# M121.net
KiCad netlist of a schematic drawn in EAGLE
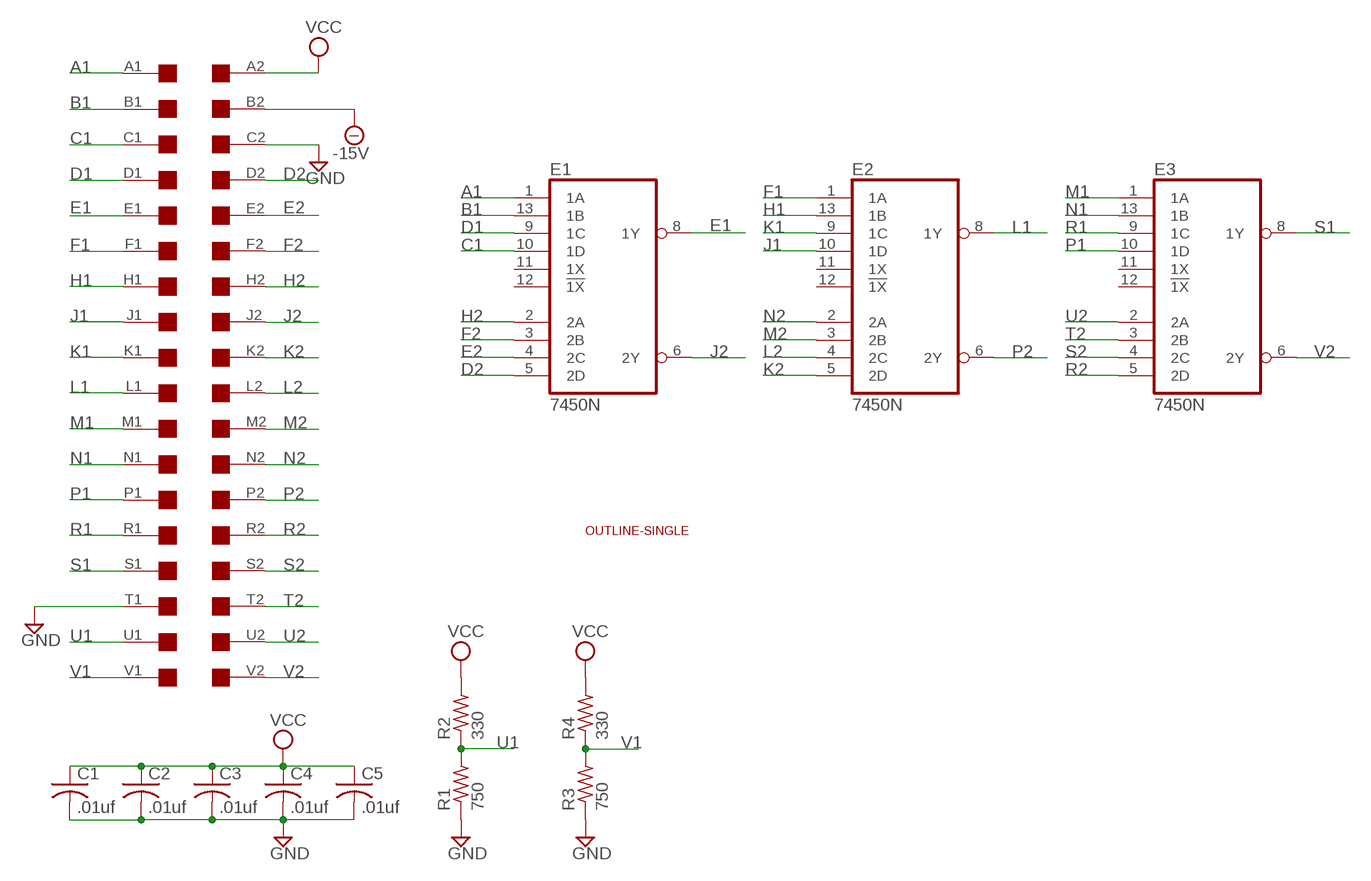
[diagram p0: schematic, sheet 1]

(export (version "E")
  (design (tool "Eeschema 10.0.6"))
  (components
    (comp (ref "C1")
      (value ".01uf")
      (footprint "eagle-import:C050-025X075")
      (libsource (lib "eagle-import") (part "C-US050-025X075"))
    )
    (comp (ref "C2")
      (value ".01uf")
      (footprint "eagle-import:C050-025X075")
      (libsource (lib "eagle-import") (part "C-US050-025X075"))
    )
    (comp (ref "C3")
      (value ".01uf")
      (footprint "eagle-import:C050-025X075")
      (libsource (lib "eagle-import") (part "C-US050-025X075"))
    )
    (comp (ref "C4")
      (value ".01uf")
      (footprint "eagle-import:C050-025X075")
      (libsource (lib "eagle-import") (part "C-US050-025X075"))
    )
    (comp (ref "C5")
      (value ".01uf")
      (footprint "eagle-import:C050-025X075")
      (libsource (lib "eagle-import") (part "C-US050-025X075"))
    )
    (comp (ref "E1")
      (value "7450N")
      (footprint "eagle-import:DIL14")
      (libsource (lib "eagle-import") (part "7450N"))
    )
    (comp (ref "E2")
      (value "7450N")
      (footprint "eagle-import:DIL14")
      (libsource (lib "eagle-import") (part "7450N"))
    )
    (comp (ref "E3")
      (value "7450N")
      (footprint "eagle-import:DIL14")
      (libsource (lib "eagle-import") (part "7450N"))
    )
    (comp (ref "R1")
      (value "750")
      (footprint "eagle-import:0207_10")
      (libsource (lib "eagle-import") (part "R-US_0207/10"))
    )
    (comp (ref "R2")
      (value "330")
      (footprint "eagle-import:0207_10")
      (libsource (lib "eagle-import") (part "R-US_0207/10"))
    )
    (comp (ref "R3")
      (value "750")
      (footprint "eagle-import:0207_10")
      (libsource (lib "eagle-import") (part "R-US_0207/10"))
    )
    (comp (ref "R4")
      (value "330")
      (footprint "eagle-import:0207_10")
      (libsource (lib "eagle-import") (part "R-US_0207/10"))
    )
    (comp (ref "U$1")
      (value "OUTLINE-SINGLE")
      (footprint "eagle-import:SINGLE")
      (libsource (lib "eagle-import") (part "OUTLINE-SINGLE"))
    )
    (comp (ref "U$4")
      (value "SINGLE")
      (footprint "eagle-import:EDGE-CON2")
      (libsource (lib "eagle-import") (part "SINGLE"))
    )
  )
  (nets
    (net (code "1") (name "-15V") (class "Default")
      (node (ref "U$4") (pin "B2") (pinfunction "1_B2") (pintype "bidirectional"))
    )
    (net (code "2") (name "/A1") (class "Default")
      (node (ref "E1") (pin "1") (pinfunction "1A_1") (pintype "input"))
      (node (ref "U$4") (pin "A1") (pinfunction "1_A1") (pintype "bidirectional"))
    )
    (net (code "3") (name "/B1") (class "Default")
      (node (ref "E1") (pin "13") (pinfunction "1B_13") (pintype "input"))
      (node (ref "U$4") (pin "B1") (pinfunction "1_B1") (pintype "bidirectional"))
    )
    (net (code "4") (name "/C1") (class "Default")
      (node (ref "E1") (pin "10") (pinfunction "1D_10") (pintype "input"))
      (node (ref "U$4") (pin "C1") (pinfunction "1_C1") (pintype "bidirectional"))
    )
    (net (code "5") (name "/D1") (class "Default")
      (node (ref "E1") (pin "9") (pinfunction "1C_9") (pintype "input"))
      (node (ref "U$4") (pin "D1") (pinfunction "1_D1") (pintype "bidirectional"))
    )
    (net (code "6") (name "/D2") (class "Default")
      (node (ref "E1") (pin "5") (pinfunction "2D_5") (pintype "input"))
      (node (ref "U$4") (pin "D2") (pinfunction "1_D2") (pintype "bidirectional"))
    )
    (net (code "7") (name "/E1") (class "Default")
      (node (ref "E1") (pin "8") (pinfunction "1Y_8") (pintype "output"))
      (node (ref "U$4") (pin "E1") (pinfunction "1_E1") (pintype "bidirectional"))
    )
    (net (code "8") (name "/E2") (class "Default")
      (node (ref "E1") (pin "4") (pinfunction "2C_4") (pintype "input"))
      (node (ref "U$4") (pin "E2") (pinfunction "1_E2") (pintype "bidirectional"))
    )
    (net (code "9") (name "/F1") (class "Default")
      (node (ref "E2") (pin "1") (pinfunction "1A_1") (pintype "input"))
      (node (ref "U$4") (pin "F1") (pinfunction "1_F1") (pintype "bidirectional"))
    )
    (net (code "10") (name "/F2") (class "Default")
      (node (ref "E1") (pin "3") (pinfunction "2B_3") (pintype "input"))
      (node (ref "U$4") (pin "F2") (pinfunction "1_F2") (pintype "bidirectional"))
    )
    (net (code "11") (name "/H1") (class "Default")
      (node (ref "E2") (pin "13") (pinfunction "1B_13") (pintype "input"))
      (node (ref "U$4") (pin "H1") (pinfunction "1_H1") (pintype "bidirectional"))
    )
    (net (code "12") (name "/H2") (class "Default")
      (node (ref "E1") (pin "2") (pinfunction "2A_2") (pintype "input"))
      (node (ref "U$4") (pin "H2") (pinfunction "1_H2") (pintype "bidirectional"))
    )
    (net (code "13") (name "/J1") (class "Default")
      (node (ref "E2") (pin "10") (pinfunction "1D_10") (pintype "input"))
      (node (ref "U$4") (pin "J1") (pinfunction "1_J1") (pintype "bidirectional"))
    )
    (net (code "14") (name "/J2") (class "Default")
      (node (ref "E1") (pin "6") (pinfunction "2Y_6") (pintype "output"))
      (node (ref "U$4") (pin "J2") (pinfunction "1_J2") (pintype "bidirectional"))
    )
    (net (code "15") (name "/K1") (class "Default")
      (node (ref "E2") (pin "9") (pinfunction "1C_9") (pintype "input"))
      (node (ref "U$4") (pin "K1") (pinfunction "1_K1") (pintype "bidirectional"))
    )
    (net (code "16") (name "/K2") (class "Default")
      (node (ref "E2") (pin "5") (pinfunction "2D_5") (pintype "input"))
      (node (ref "U$4") (pin "K2") (pinfunction "1_K2") (pintype "bidirectional"))
    )
    (net (code "17") (name "/L1") (class "Default")
      (node (ref "E2") (pin "8") (pinfunction "1Y_8") (pintype "output"))
      (node (ref "U$4") (pin "L1") (pinfunction "1_L1") (pintype "bidirectional"))
    )
    (net (code "18") (name "/L2") (class "Default")
      (node (ref "E2") (pin "4") (pinfunction "2C_4") (pintype "input"))
      (node (ref "U$4") (pin "L2") (pinfunction "1_L2") (pintype "bidirectional"))
    )
    (net (code "19") (name "/M1") (class "Default")
      (node (ref "E3") (pin "1") (pinfunction "1A_1") (pintype "input"))
      (node (ref "U$4") (pin "M1") (pinfunction "1_M1") (pintype "bidirectional"))
    )
    (net (code "20") (name "/M2") (class "Default")
      (node (ref "E2") (pin "3") (pinfunction "2B_3") (pintype "input"))
      (node (ref "U$4") (pin "M2") (pinfunction "1_M2") (pintype "bidirectional"))
    )
    (net (code "21") (name "/N1") (class "Default")
      (node (ref "E3") (pin "13") (pinfunction "1B_13") (pintype "input"))
      (node (ref "U$4") (pin "N1") (pinfunction "1_N1") (pintype "bidirectional"))
    )
    (net (code "22") (name "/N2") (class "Default")
      (node (ref "E2") (pin "2") (pinfunction "2A_2") (pintype "input"))
      (node (ref "U$4") (pin "N2") (pinfunction "1_N2") (pintype "bidirectional"))
    )
    (net (code "23") (name "/P1") (class "Default")
      (node (ref "E3") (pin "10") (pinfunction "1D_10") (pintype "input"))
      (node (ref "U$4") (pin "P1") (pinfunction "1_P1") (pintype "bidirectional"))
    )
    (net (code "24") (name "/P2") (class "Default")
      (node (ref "E2") (pin "6") (pinfunction "2Y_6") (pintype "output"))
      (node (ref "U$4") (pin "P2") (pinfunction "1_P2") (pintype "bidirectional"))
    )
    (net (code "25") (name "/R1") (class "Default")
      (node (ref "E3") (pin "9") (pinfunction "1C_9") (pintype "input"))
      (node (ref "U$4") (pin "R1") (pinfunction "1_R1") (pintype "bidirectional"))
    )
    (net (code "26") (name "/R2") (class "Default")
      (node (ref "E3") (pin "5") (pinfunction "2D_5") (pintype "input"))
      (node (ref "U$4") (pin "R2") (pinfunction "1_R2") (pintype "bidirectional"))
    )
    (net (code "27") (name "/S1") (class "Default")
      (node (ref "E3") (pin "8") (pinfunction "1Y_8") (pintype "output"))
      (node (ref "U$4") (pin "S1") (pinfunction "1_S1") (pintype "bidirectional"))
    )
    (net (code "28") (name "/S2") (class "Default")
      (node (ref "E3") (pin "4") (pinfunction "2C_4") (pintype "input"))
      (node (ref "U$4") (pin "S2") (pinfunction "1_S2") (pintype "bidirectional"))
    )
    (net (code "29") (name "/T2") (class "Default")
      (node (ref "E3") (pin "3") (pinfunction "2B_3") (pintype "input"))
      (node (ref "U$4") (pin "T2") (pinfunction "1_T2") (pintype "bidirectional"))
    )
    (net (code "30") (name "/U1") (class "Default")
      (node (ref "R1") (pin "2") (pinfunction "2_2") (pintype "passive"))
      (node (ref "R2") (pin "1") (pinfunction "1_1") (pintype "passive"))
      (node (ref "U$4") (pin "U1") (pinfunction "1_U1") (pintype "bidirectional"))
    )
    (net (code "31") (name "/U2") (class "Default")
      (node (ref "E3") (pin "2") (pinfunction "2A_2") (pintype "input"))
      (node (ref "U$4") (pin "U2") (pinfunction "1_U2") (pintype "bidirectional"))
    )
    (net (code "32") (name "/V1") (class "Default")
      (node (ref "R3") (pin "2") (pinfunction "2_2") (pintype "passive"))
      (node (ref "R4") (pin "1") (pinfunction "1_1") (pintype "passive"))
      (node (ref "U$4") (pin "V1") (pinfunction "1_V1") (pintype "bidirectional"))
    )
    (net (code "33") (name "/V2") (class "Default")
      (node (ref "E3") (pin "6") (pinfunction "2Y_6") (pintype "output"))
      (node (ref "U$4") (pin "V2") (pinfunction "1_V2") (pintype "bidirectional"))
    )
    (net (code "34") (name "GND") (class "Default")
      (node (ref "C1") (pin "2") (pinfunction "2_2") (pintype "passive"))
      (node (ref "C2") (pin "2") (pinfunction "2_2") (pintype "passive"))
      (node (ref "C3") (pin "2") (pinfunction "2_2") (pintype "passive"))
      (node (ref "C4") (pin "2") (pinfunction "2_2") (pintype "passive"))
      (node (ref "C5") (pin "2") (pinfunction "2_2") (pintype "passive"))
      (node (ref "R1") (pin "1") (pinfunction "1_1") (pintype "passive"))
      (node (ref "R3") (pin "1") (pinfunction "1_1") (pintype "passive"))
      (node (ref "U$4") (pin "C2") (pinfunction "1_C2") (pintype "bidirectional"))
      (node (ref "U$4") (pin "T1") (pinfunction "1_T1") (pintype "bidirectional"))
    )
    (net (code "35") (name "VCC") (class "Default")
      (node (ref "C1") (pin "1") (pinfunction "1_1") (pintype "passive"))
      (node (ref "C2") (pin "1") (pinfunction "1_1") (pintype "passive"))
      (node (ref "C3") (pin "1") (pinfunction "1_1") (pintype "passive"))
      (node (ref "C4") (pin "1") (pinfunction "1_1") (pintype "passive"))
      (node (ref "C5") (pin "1") (pinfunction "1_1") (pintype "passive"))
      (node (ref "R2") (pin "2") (pinfunction "2_2") (pintype "passive"))
      (node (ref "R4") (pin "2") (pinfunction "2_2") (pintype "passive"))
      (node (ref "U$4") (pin "A2") (pinfunction "1_A2") (pintype "bidirectional"))
    )
    (net (code "36") (name "unconnected-(E1A-1X-Pad11)") (class "Default")
      (node (ref "E1") (pin "11") (pinfunction "1X_11") (pintype "input"))
    )
    (net (code "37") (name "unconnected-(E1A-~{1X}-Pad12)") (class "Default")
      (node (ref "E1") (pin "12") (pinfunction "~{1X}_12") (pintype "input"))
    )
    (net (code "38") (name "unconnected-(E2A-1X-Pad11)") (class "Default")
      (node (ref "E2") (pin "11") (pinfunction "1X_11") (pintype "input"))
    )
    (net (code "39") (name "unconnected-(E2A-~{1X}-Pad12)") (class "Default")
      (node (ref "E2") (pin "12") (pinfunction "~{1X}_12") (pintype "input"))
    )
    (net (code "40") (name "unconnected-(E3A-1X-Pad11)") (class "Default")
      (node (ref "E3") (pin "11") (pinfunction "1X_11") (pintype "input"))
    )
    (net (code "41") (name "unconnected-(E3A-~{1X}-Pad12)") (class "Default")
      (node (ref "E3") (pin "12") (pinfunction "~{1X}_12") (pintype "input"))
    )
  )
)
